# AccelerometerSchematic.net
KiCad netlist of a schematic drawn in Altium Designer
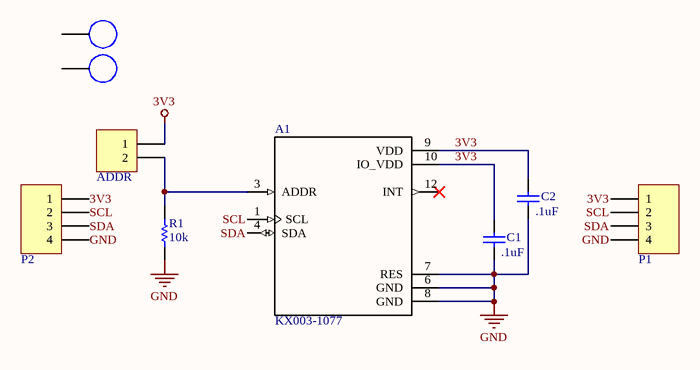
[diagram p0: AccelerometerSchematic.SchDoc]

(export (version "E")
  (design (tool "Eeschema 10.0.6"))
  (components
    (comp (ref "A1")
      (value "KX003-1077")
      (footprint "*XDCR_KX003-1077")
      (description "Accelerometer X, Y, Z Axis Â±2g, 4g, 8g, 16g 3.5kHz _X,Y_, 1.8kHz _Z_ 12-LGA _2x2_")
      (fields
        (field (name "DIGI-KEY_PART_NUMBER") "KX003-1077CT-ND")
        (field (name "MF") "Rohm Semiconductor")
      )
      (libsource (lib "KX003-1077") (part "KX003-1077"))
    )
    (comp (ref "ADDR")
      (value "90120-0122")
      (footprint "HDR1X2")
      (description "MOLEX CONN HEADER 2POS .100\" STR TIN")
      (libsource (lib "AltiumGFU64") (part "Header 2"))
    )
    (comp (ref "C1")
      (value ".1uF")
      (footprint "0805")
      (description ".1, 10%, 50V")
      (fields (field (name "GFUPARTNO") "CL21A475KPFNNNE"))
      (libsource (lib "AltiumGFU64") (part "Cap"))
    )
    (comp (ref "C2")
      (value ".1uF")
      (footprint "0805")
      (description ".1, 10%, 50V")
      (fields (field (name "GFUPARTNO") "CL21A475KPFNNNE"))
      (libsource (lib "AltiumGFU64") (part "Cap"))
    )
    (comp (ref "DR1")
      (value "4-40 DRILL HOLE")
      (footprint "4_40 DRILL HOLE")
      (description "Mounting hole for 4-40 screw, non-BOM")
      (fields (field (name "GFUPARTNO") "4_40 DRILL HOLE"))
      (libsource (lib "AltiumGFU64") (part "8_32 DRILL HOLE"))
    )
    (comp (ref "DR2")
      (value "4-40 DRILL HOLE")
      (footprint "4_40 DRILL HOLE")
      (description "Mounting hole for 4-40 screw, non-BOM")
      (fields (field (name "GFUPARTNO") "4_40 DRILL HOLE"))
      (libsource (lib "AltiumGFU64") (part "8_32 DRILL HOLE"))
    )
    (comp (ref "P1")
      (value "90120-0124")
      (footprint "HDR1X4")
      (description "CONN HEADER 4POS .100\" STR TIN")
      (libsource (lib "") (part "Header 4_1"))
    )
    (comp (ref "P2")
      (value "90120-0124")
      (footprint "HDR1X4")
      (description "CONN HEADER 4POS .100\" STR TIN")
      (libsource (lib "AltiumGFU64") (part "Header 4"))
    )
    (comp (ref "R1")
      (value "10k")
      (footprint "0805_RES_HD")
      (description "RES 10K OHM 1/8W 5% 0805")
      (fields (field (name "GFUPARTNO") "RC2012F752CS"))
      (libsource (lib "AltiumGFU64") (part "ResBasic"))
    )
  )
  (nets
    (net (code "1") (name "/SCL") (class "Default")
      (node (ref "A1") (pin "1") (pinfunction "SCL_1") (pintype "input"))
      (node (ref "P1") (pin "2") (pinfunction "2_2") (pintype "passive"))
      (node (ref "P2") (pin "2") (pinfunction "2_2") (pintype "passive"))
    )
    (net (code "2") (name "/SDA") (class "Default")
      (node (ref "A1") (pin "4") (pinfunction "SDA_4") (pintype "bidirectional"))
      (node (ref "P1") (pin "3") (pinfunction "3_3") (pintype "passive"))
      (node (ref "P2") (pin "3") (pinfunction "3_3") (pintype "passive"))
    )
    (net (code "3") (name "3V3") (class "Default")
      (node (ref "A1") (pin "10") (pinfunction "IO_VDD_10") (pintype "power_in"))
      (node (ref "A1") (pin "9") (pinfunction "VDD_9") (pintype "power_in"))
      (node (ref "ADDR") (pin "1") (pinfunction "1_1") (pintype "passive"))
      (node (ref "C1") (pin "2") (pinfunction "2_2") (pintype "passive"))
      (node (ref "C2") (pin "2") (pinfunction "2_2") (pintype "passive"))
      (node (ref "P1") (pin "1") (pinfunction "1_1") (pintype "passive"))
      (node (ref "P2") (pin "1") (pinfunction "1_1") (pintype "passive"))
    )
    (net (code "4") (name "GND") (class "Default")
      (node (ref "A1") (pin "6") (pinfunction "GND_6") (pintype "power_in"))
      (node (ref "A1") (pin "7") (pinfunction "RES_7") (pintype "power_in"))
      (node (ref "A1") (pin "8") (pinfunction "GND_8") (pintype "power_in"))
      (node (ref "C1") (pin "1") (pinfunction "1_1") (pintype "passive"))
      (node (ref "C2") (pin "1") (pinfunction "1_1") (pintype "passive"))
      (node (ref "P1") (pin "4") (pinfunction "4_4") (pintype "passive"))
      (node (ref "P2") (pin "4") (pinfunction "4_4") (pintype "passive"))
      (node (ref "R1") (pin "1") (pinfunction "1_1") (pintype "passive"))
    )
    (net (code "5") (name "Net-(A1-ADDR)") (class "Default")
      (node (ref "A1") (pin "3") (pinfunction "ADDR_3") (pintype "input"))
      (node (ref "ADDR") (pin "2") (pinfunction "2_2") (pintype "passive"))
      (node (ref "R1") (pin "2") (pinfunction "2_2") (pintype "passive"))
    )
    (net (code "6") (name "unconnected-(A1-INT-Pad12)") (class "Default")
      (node (ref "A1") (pin "12") (pinfunction "INT_12") (pintype "output+no_connect"))
    )
    (net (code "7") (name "unconnected-(DR1-Pad0)") (class "Default")
      (node (ref "DR1") (pin "0") (pinfunction "0_0") (pintype "passive"))
    )
    (net (code "8") (name "unconnected-(DR2-Pad0)") (class "Default")
      (node (ref "DR2") (pin "0") (pinfunction "0_0") (pintype "passive"))
    )
  )
)
